# SCH_Arduino-Train-v_2_2026-08-14.net
KiCad netlist of a schematic drawn in EasyEDA
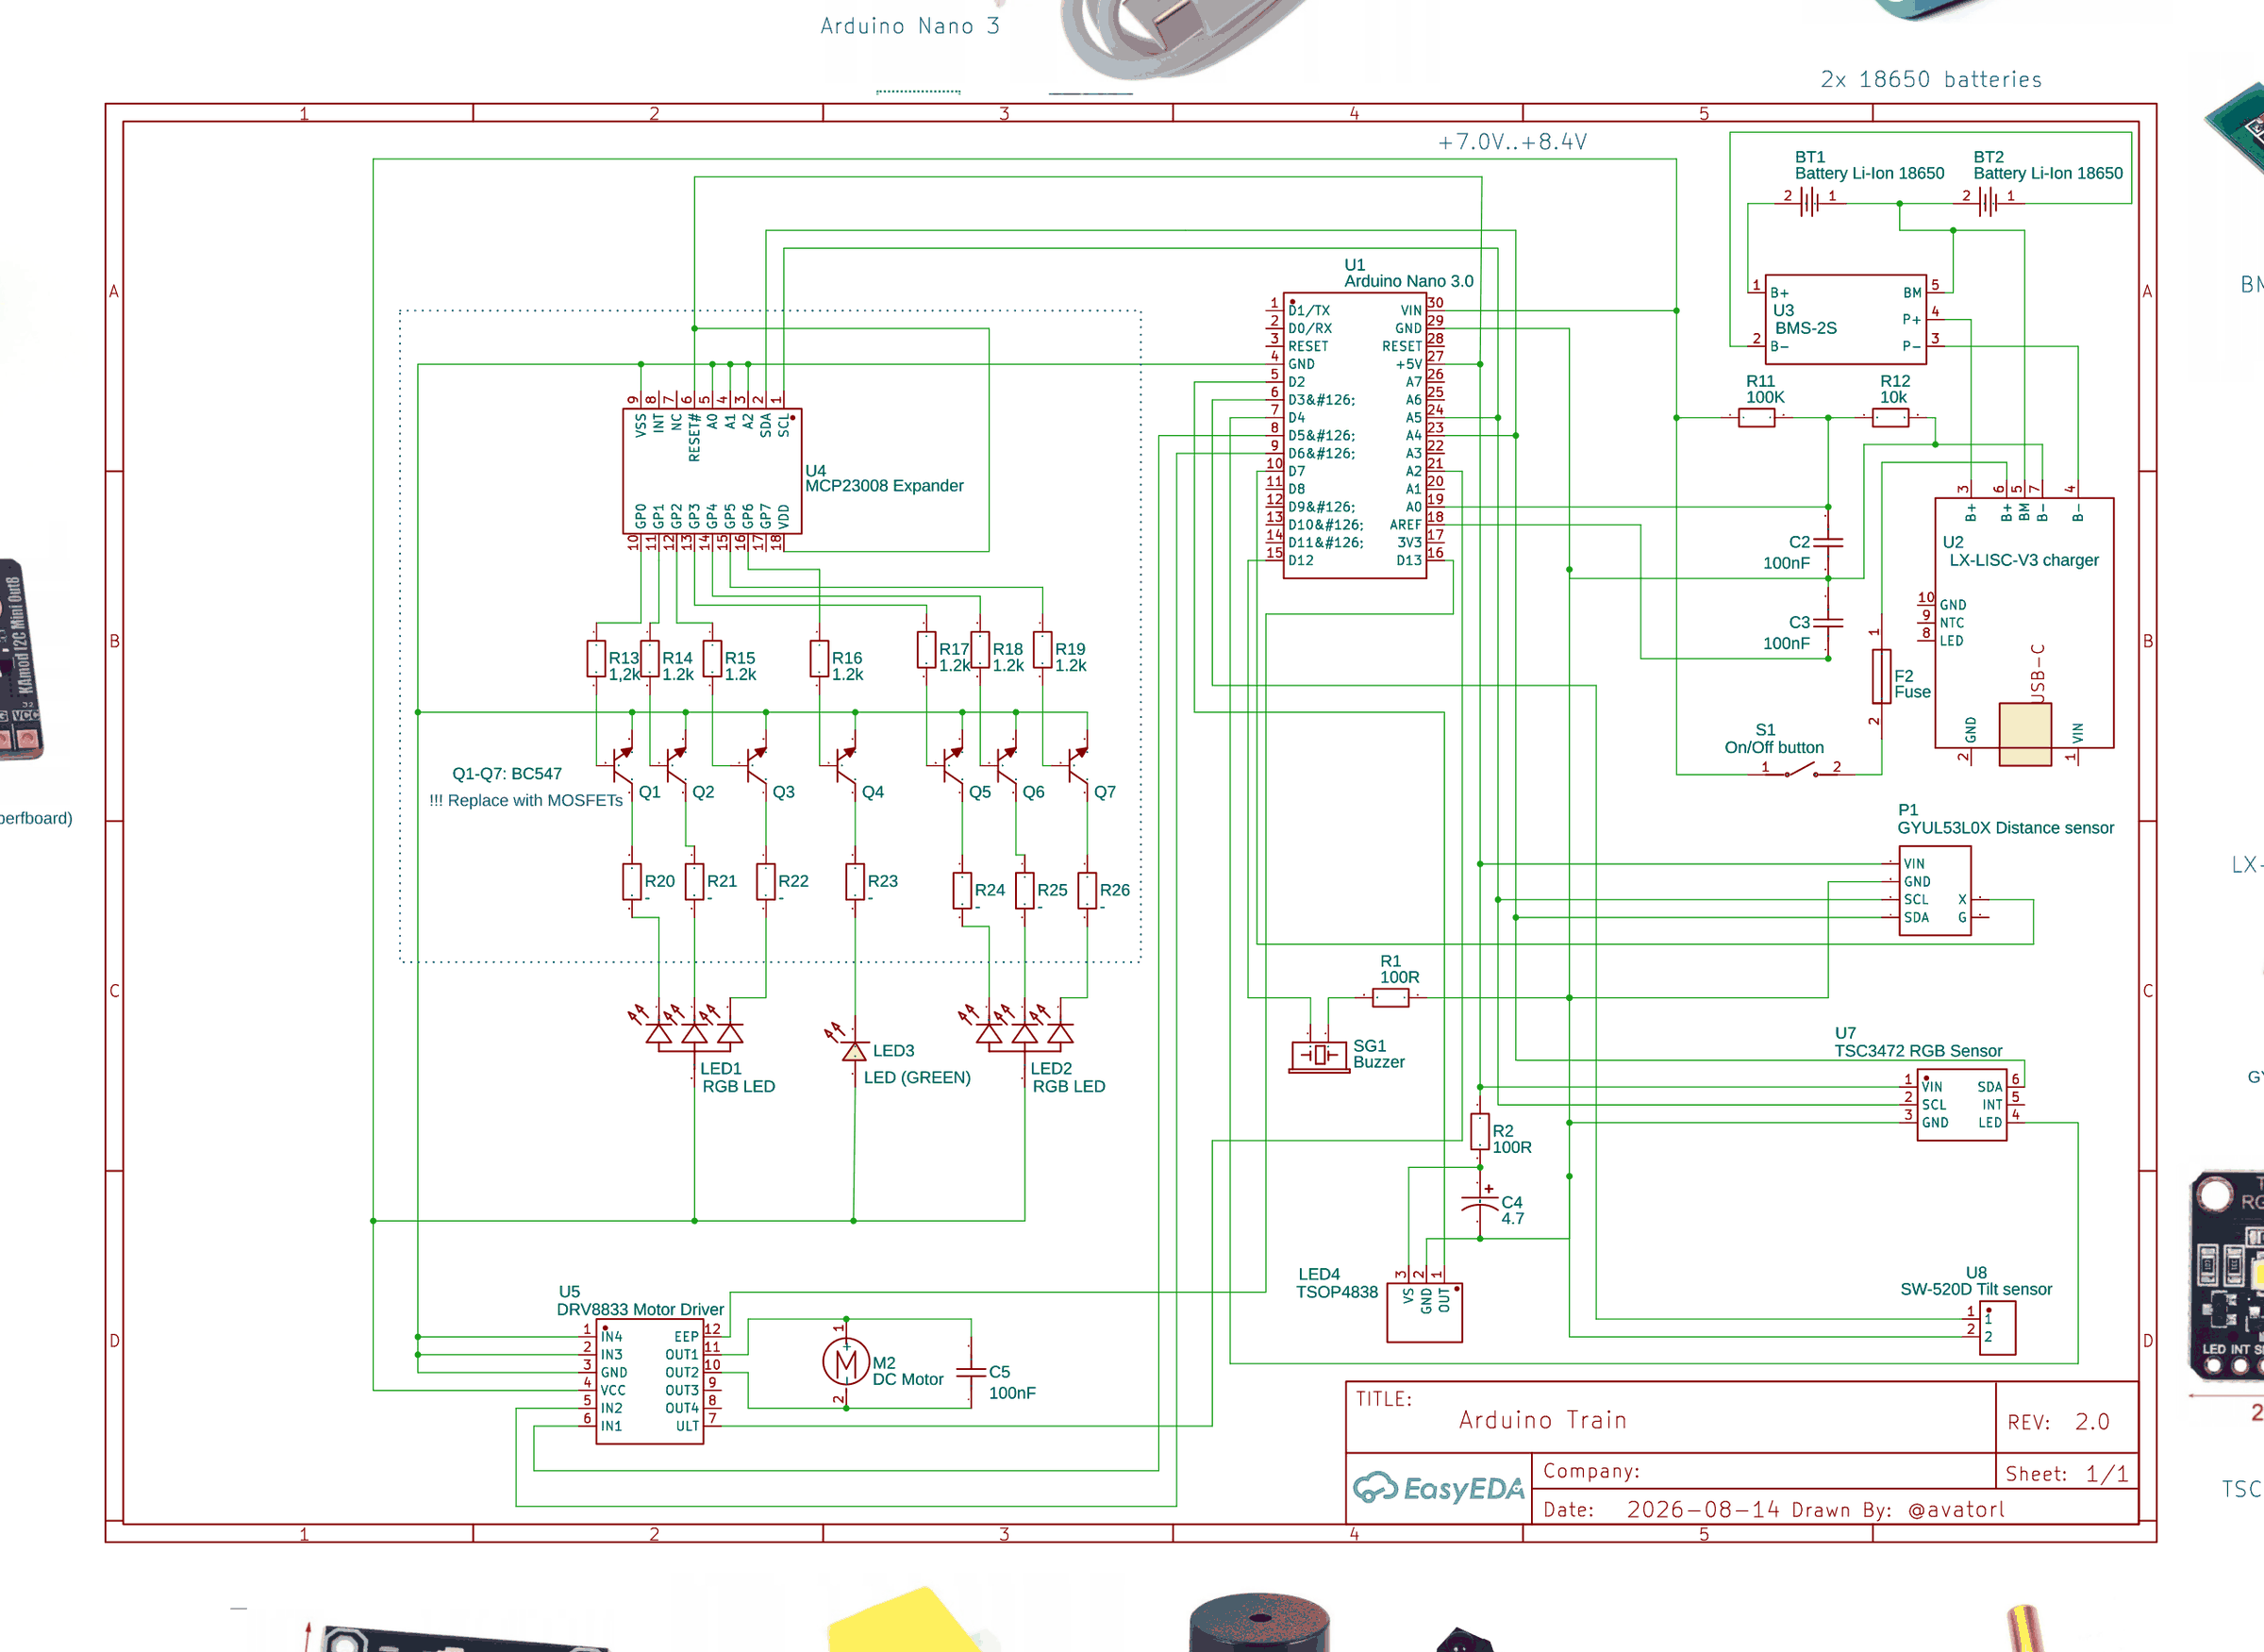
[diagram p0: schematic sheet]

(export (version "E")
  (design (tool "Eeschema 10.0.6"))
  (components
    (comp (ref "BT1")
      (value "Battery Li-Ion 18650")
      (fields
        (field (name "Manufacturer Part") "BH-18650-B1BA002")
        (field (name "Manufacturer") "MYOUNG(美阳)")
      )
      (libsource (lib "") (part "BH-18650-B1BA002"))
    )
    (comp (ref "BT2")
      (value "Battery Li-Ion 18650")
      (fields
        (field (name "Manufacturer Part") "BH-18650-B1BA002")
        (field (name "Manufacturer") "MYOUNG(美阳)")
      )
      (libsource (lib "") (part "BH-18650-B1BA002"))
    )
    (comp (ref "C2") (value "100nF") (libsource (lib "") (part "C_0603_US_1")))
    (comp (ref "C3") (value "100nF") (libsource (lib "") (part "C_0603_US_1")))
    (comp (ref "C4")
      (value "4.7")
      (fields (field (name "Manufacturer Part") "B32672P5105J000") (field (name "Manufacturer") "TDK"))
      (libsource (lib "") (part "C_Tan_SMD_A_US"))
    )
    (comp (ref "C5") (value "100nF") (libsource (lib "") (part "C_0603_US")))
    (comp (ref "F2") (value "Fuse") (libsource (lib "") (part "FUSE BLADE_PCB_MOUNT COPY")))
    (comp (ref "LED1")
      (value "RGB LED")
      (fields (field (name "Manufacturer Part") "3528反贴RGB 6028反贴RGB 缺口蓝色"))
      (libsource (lib "") (part "3528RGB 6028RGB"))
    )
    (comp (ref "LED2")
      (value "RGB LED")
      (fields (field (name "Manufacturer Part") "3528反贴RGB 6028反贴RGB 缺口蓝色"))
      (libsource (lib "") (part "3528RGB 6028RGB"))
    )
    (comp (ref "LED3")
      (value "LED (GREEN)")
      (fields (field (name "Manufacturer Part") "LED三色(Red,Yellow,Green)"))
      (libsource (lib "") (part "LED (GREEN)"))
    )
    (comp (ref "LED4")
      (value "TSOP4838")
      (fields (field (name "Manufacturer") "VISHAY(威世)"))
      (libsource (lib "") (part "TSOP4838"))
    )
    (comp (ref "M2") (value "DC Motor") (libsource (lib "") (part "Motor_DC")))
    (comp (ref "P1")
      (value "GYUL53L0X Distance sensor")
      (fields (field (name "Manufacturer Part") "IDC Box 2X4 2.54MM") (field (name "Manufacturer") "BOOMELE"))
      (libsource (lib "") (part "GYUL53L0X_UPDATED final"))
    )
    (comp (ref "Q1")
      (value "Q1-Q7: BC547")
      (fields
        (field (name "Manufacturer Part") "BC547(RANGE:420-800)")
        (field (name "Manufacturer") "CJ(江苏长电/长晶)")
      )
      (libsource (lib "") (part "BC547"))
    )
    (comp (ref "Q2")
      (value "BC547")
      (fields
        (field (name "Manufacturer Part") "BC547(RANGE:420-800)")
        (field (name "Manufacturer") "CJ(江苏长电/长晶)")
      )
      (libsource (lib "") (part "BC547"))
    )
    (comp (ref "Q3")
      (value "BC547")
      (fields
        (field (name "Manufacturer Part") "BC547(RANGE:420-800)")
        (field (name "Manufacturer") "CJ(江苏长电/长晶)")
      )
      (libsource (lib "") (part "BC547"))
    )
    (comp (ref "Q4")
      (value "BC547")
      (fields
        (field (name "Manufacturer Part") "BC547(RANGE:420-800)")
        (field (name "Manufacturer") "CJ(江苏长电/长晶)")
      )
      (libsource (lib "") (part "BC547"))
    )
    (comp (ref "Q5")
      (value "BC547")
      (fields
        (field (name "Manufacturer Part") "BC547(RANGE:420-800)")
        (field (name "Manufacturer") "CJ(江苏长电/长晶)")
      )
      (libsource (lib "") (part "BC547"))
    )
    (comp (ref "Q6")
      (value "BC547")
      (fields
        (field (name "Manufacturer Part") "BC547(RANGE:420-800)")
        (field (name "Manufacturer") "CJ(江苏长电/长晶)")
      )
      (libsource (lib "") (part "BC547"))
    )
    (comp (ref "Q7")
      (value "BC547")
      (fields
        (field (name "Manufacturer Part") "BC547(RANGE:420-800)")
        (field (name "Manufacturer") "CJ(江苏长电/长晶)")
      )
      (libsource (lib "") (part "BC547"))
    )
    (comp (ref "R1") (value "100R") (libsource (lib "") (part "R_0603_EU_2")))
    (comp (ref "R2") (value "100R") (libsource (lib "") (part "R_0603_EU")))
    (comp (ref "R11") (value "100K") (libsource (lib "") (part "R_0603_EU_1")))
    (comp (ref "R12") (value "10k") (libsource (lib "") (part "R_0603_EU_1")))
    (comp (ref "R13") (value "1,2k") (libsource (lib "") (part "R_0603_EU")))
    (comp (ref "R14") (value "1.2k") (libsource (lib "") (part "R_0603_EU")))
    (comp (ref "R15") (value "1.2k") (libsource (lib "") (part "R_0603_EU")))
    (comp (ref "R16") (value "1.2k") (libsource (lib "") (part "R_0603_EU")))
    (comp (ref "R17") (value "1.2k") (libsource (lib "") (part "R_0603_EU")))
    (comp (ref "R18") (value "1.2k") (libsource (lib "") (part "R_0603_EU")))
    (comp (ref "R19") (value "1.2k") (libsource (lib "") (part "R_0603_EU")))
    (comp (ref "R20") (value "-") (libsource (lib "") (part "R_0603_EU")))
    (comp (ref "R21") (value "-") (libsource (lib "") (part "R_0603_EU")))
    (comp (ref "R22") (value "-") (libsource (lib "") (part "R_0603_EU")))
    (comp (ref "R23") (value "-") (libsource (lib "") (part "R_0603_EU")))
    (comp (ref "R24") (value "-") (libsource (lib "") (part "R_0603_EU")))
    (comp (ref "R25") (value "-") (libsource (lib "") (part "R_0603_EU")))
    (comp (ref "R26") (value "-") (libsource (lib "") (part "R_0603_EU")))
    (comp (ref "S1")
      (value "On/Off button")
      (fields (field (name "Manufacturer Part") "BUTTON"))
      (libsource (lib "") (part "BUTTON"))
    )
    (comp (ref "SG1") (value "Buzzer") (libsource (lib "") (part "BUZZER")))
    (comp (ref "U1")
      (value "Arduino Nano 3.0")
      (fields (field (name "Manufacturer Part") "ARDUINO_NANO"))
      (libsource (lib "") (part "ARDUINO_NANO"))
    )
    (comp (ref "U2") (value "LX-LISC-V3 charger") (libsource (lib "") (part "LX-LISC-V1")))
    (comp (ref "U3")
      (value "BMS-2S")
      (fields (field (name "Manufacturer Part") "HX-2S-D01"))
      (libsource (lib "") (part "2S 3A-10A Lithium Li-ion 18650 Battery BMS Protection PCB Board 7.4v/8.4V"))
    )
    (comp (ref "U4")
      (value "MCP23008 Expander")
      (fields
        (field (name "Manufacturer Part") "MCP23008-E/P")
        (field (name "Manufacturer") "MICROCHIP(美国微芯)")
      )
      (libsource (lib "") (part "MCP23008-E/P"))
    )
    (comp (ref "U5")
      (value "DRV8833 Motor Driver")
      (fields (field (name "Manufacturer Part") "DRV8833"))
      (libsource (lib "") (part "DRV8833 - Motor Driver"))
    )
    (comp (ref "U7")
      (value "TSC3472 RGB Sensor")
      (fields (field (name "Manufacturer Part") "TCS34725FN") (field (name "Manufacturer") "ams(艾迈斯半导体)"))
      (libsource (lib "") (part "TCS34725FN"))
    )
    (comp (ref "U8")
      (value "SW-520D Tilt sensor")
      (fields (field (name "Manufacturer Part") "SW-520D") (field (name "Manufacturer") "SHOU HAN(首韩)"))
      (libsource (lib "") (part "SW-520D"))
    )
  )
  (nets
    (net (code "1") (name "Net-(F2-Pad1)") (class "Default")
      (node (ref "F2") (pin "1") (pinfunction "1_1") (pintype "unspecified"))
      (node (ref "U2") (pin "6") (pinfunction "B+_6") (pintype "unspecified"))
    )
    (net (code "2") (name "Net-(F2-Pad2)") (class "Default")
      (node (ref "F2") (pin "2") (pinfunction "2_2") (pintype "unspecified"))
      (node (ref "S1") (pin "2") (pinfunction "2_2") (pintype "unspecified"))
    )
    (net (code "3") (name "Net-(LED1-A)") (class "Default")
      (node (ref "LED1") (pin "3") (pinfunction "A_3") (pintype "unspecified"))
      (node (ref "LED2") (pin "3") (pinfunction "A_3") (pintype "unspecified"))
      (node (ref "LED3") (pin "2") (pinfunction "2_2") (pintype "unspecified"))
      (node (ref "R11") (pin "1") (pinfunction "1_1") (pintype "unspecified"))
      (node (ref "S1") (pin "1") (pinfunction "1_1") (pintype "unspecified"))
      (node (ref "U1") (pin "30") (pinfunction "VIN_30") (pintype "unspecified"))
      (node (ref "U5") (pin "4") (pinfunction "VCC_4") (pintype "unspecified"))
    )
    (net (code "4") (name "Net-(LED1-B)") (class "Default")
      (node (ref "LED1") (pin "1") (pinfunction "B_1") (pintype "unspecified"))
      (node (ref "R21") (pin "2") (pinfunction "2_2") (pintype "unspecified"))
    )
    (net (code "5") (name "Net-(LED1-G)") (class "Default")
      (node (ref "LED1") (pin "4") (pinfunction "G_4") (pintype "unspecified"))
      (node (ref "R20") (pin "2") (pinfunction "2_2") (pintype "unspecified"))
    )
    (net (code "6") (name "Net-(LED1-R)") (class "Default")
      (node (ref "LED1") (pin "2") (pinfunction "R_2") (pintype "unspecified"))
      (node (ref "R22") (pin "2") (pinfunction "2_2") (pintype "unspecified"))
    )
    (net (code "7") (name "Net-(LED2-B)") (class "Default")
      (node (ref "LED2") (pin "1") (pinfunction "B_1") (pintype "unspecified"))
      (node (ref "R25") (pin "2") (pinfunction "2_2") (pintype "unspecified"))
    )
    (net (code "8") (name "Net-(LED2-G)") (class "Default")
      (node (ref "LED2") (pin "4") (pinfunction "G_4") (pintype "unspecified"))
      (node (ref "R24") (pin "2") (pinfunction "2_2") (pintype "unspecified"))
    )
    (net (code "9") (name "Net-(LED2-R)") (class "Default")
      (node (ref "LED2") (pin "2") (pinfunction "R_2") (pintype "unspecified"))
      (node (ref "R26") (pin "2") (pinfunction "2_2") (pintype "unspecified"))
    )
    (net (code "10") (name "Net-(LED3-Pad1)") (class "Default")
      (node (ref "LED3") (pin "1") (pinfunction "1_1") (pintype "unspecified"))
      (node (ref "R23") (pin "2") (pinfunction "2_2") (pintype "unspecified"))
    )
    (net (code "11") (name "Net-(LED4-GND)") (class "Default")
      (node (ref "C2") (pin "1") (pinfunction "1_1") (pintype "unspecified"))
      (node (ref "C3") (pin "2") (pinfunction "2_2") (pintype "unspecified"))
      (node (ref "C4") (pin "2") (pinfunction "2_2") (pintype "unspecified"))
      (node (ref "LED4") (pin "2") (pinfunction "GND_2") (pintype "unspecified"))
      (node (ref "P1") (pin "3") (pinfunction "GND_3") (pintype "unspecified"))
      (node (ref "R1") (pin "1") (pinfunction "1_1") (pintype "unspecified"))
      (node (ref "R12") (pin "2") (pinfunction "2_2") (pintype "unspecified"))
      (node (ref "U1") (pin "29") (pinfunction "GND_29") (pintype "unspecified"))
      (node (ref "U2") (pin "7") (pinfunction "B-_7") (pintype "unspecified"))
      (node (ref "U7") (pin "3") (pinfunction "GND_3") (pintype "unspecified"))
      (node (ref "U8") (pin "2") (pinfunction "2_2") (pintype "unspecified"))
    )
    (net (code "12") (name "Net-(LED4-OUT)") (class "Default")
      (node (ref "LED4") (pin "1") (pinfunction "OUT_1") (pintype "unspecified"))
      (node (ref "U1") (pin "5") (pinfunction "D2_5") (pintype "unspecified"))
    )
    (net (code "13") (name "Net-(LED4-VS)") (class "Default")
      (node (ref "C4") (pin "1") (pinfunction "1_1") (pintype "unspecified"))
      (node (ref "LED4") (pin "3") (pinfunction "VS_3") (pintype "unspecified"))
      (node (ref "R2") (pin "2") (pinfunction "2_2") (pintype "unspecified"))
    )
    (net (code "14") (name "Net-(M2-+)") (class "Default")
      (node (ref "C5") (pin "2") (pinfunction "2_2") (pintype "unspecified"))
      (node (ref "M2") (pin "1") (pinfunction "+_1") (pintype "unspecified"))
      (node (ref "U5") (pin "11") (pinfunction "OUT1_11") (pintype "unspecified"))
    )
    (net (code "15") (name "Net-(M2--)") (class "Default")
      (node (ref "C5") (pin "1") (pinfunction "1_1") (pintype "unspecified"))
      (node (ref "M2") (pin "2") (pinfunction "-_2") (pintype "unspecified"))
      (node (ref "U5") (pin "10") (pinfunction "OUT2_10") (pintype "unspecified"))
    )
    (net (code "16") (name "Net-(P1-SCL)") (class "Default")
      (node (ref "P1") (pin "5") (pinfunction "SCL_5") (pintype "unspecified"))
      (node (ref "U1") (pin "24") (pinfunction "A5_24") (pintype "unspecified"))
      (node (ref "U4") (pin "1") (pinfunction "SCL_1") (pintype "unspecified"))
      (node (ref "U7") (pin "2") (pinfunction "SCL_2") (pintype "unspecified"))
    )
    (net (code "17") (name "Net-(P1-SDA)") (class "Default")
      (node (ref "P1") (pin "7") (pinfunction "SDA_7") (pintype "unspecified"))
      (node (ref "U1") (pin "23") (pinfunction "A4_23") (pintype "unspecified"))
      (node (ref "U4") (pin "2") (pinfunction "SDA_2") (pintype "unspecified"))
      (node (ref "U7") (pin "6") (pinfunction "SDA_6") (pintype "unspecified"))
    )
    (net (code "18") (name "Net-(P1-VIN)") (class "Default")
      (node (ref "P1") (pin "1") (pinfunction "VIN_1") (pintype "unspecified"))
      (node (ref "R2") (pin "1") (pinfunction "1_1") (pintype "unspecified"))
      (node (ref "U1") (pin "27") (pinfunction "+5V_27") (pintype "unspecified"))
      (node (ref "U4") (pin "18") (pinfunction "VDD_18") (pintype "unspecified"))
      (node (ref "U4") (pin "6") (pinfunction "RESET#_6") (pintype "unspecified"))
      (node (ref "U7") (pin "1") (pinfunction "VIN_1") (pintype "unspecified"))
    )
    (net (code "19") (name "Net-(P1-X)") (class "Default")
      (node (ref "P1") (pin "6") (pinfunction "X_6") (pintype "unspecified"))
      (node (ref "U1") (pin "10") (pinfunction "D7_10") (pintype "unspecified"))
    )
    (net (code "20") (name "Net-(Q1-B)") (class "Default")
      (node (ref "Q1") (pin "2") (pinfunction "B_2") (pintype "unspecified"))
      (node (ref "R13") (pin "2") (pinfunction "2_2") (pintype "unspecified"))
    )
    (net (code "21") (name "Net-(Q1-C)") (class "Default")
      (node (ref "Q1") (pin "1") (pinfunction "C_1") (pintype "unspecified"))
      (node (ref "R20") (pin "1") (pinfunction "1_1") (pintype "unspecified"))
    )
    (net (code "22") (name "Net-(Q1-E)") (class "Default")
      (node (ref "Q1") (pin "3") (pinfunction "E_3") (pintype "unspecified"))
      (node (ref "Q2") (pin "3") (pinfunction "E_3") (pintype "unspecified"))
      (node (ref "Q3") (pin "3") (pinfunction "E_3") (pintype "unspecified"))
      (node (ref "Q4") (pin "3") (pinfunction "E_3") (pintype "unspecified"))
      (node (ref "Q5") (pin "3") (pinfunction "E_3") (pintype "unspecified"))
      (node (ref "Q6") (pin "3") (pinfunction "E_3") (pintype "unspecified"))
      (node (ref "Q7") (pin "3") (pinfunction "E_3") (pintype "unspecified"))
      (node (ref "U1") (pin "4") (pinfunction "GND_4") (pintype "unspecified"))
      (node (ref "U4") (pin "3") (pinfunction "A2_3") (pintype "unspecified"))
      (node (ref "U4") (pin "4") (pinfunction "A1_4") (pintype "unspecified"))
      (node (ref "U4") (pin "5") (pinfunction "A0_5") (pintype "unspecified"))
      (node (ref "U4") (pin "9") (pinfunction "VSS_9") (pintype "unspecified"))
      (node (ref "U5") (pin "1") (pinfunction "IN4_1") (pintype "unspecified"))
      (node (ref "U5") (pin "2") (pinfunction "IN3_2") (pintype "unspecified"))
      (node (ref "U5") (pin "3") (pinfunction "GND_3") (pintype "unspecified"))
    )
    (net (code "23") (name "Net-(Q2-B)") (class "Default")
      (node (ref "Q2") (pin "2") (pinfunction "B_2") (pintype "unspecified"))
      (node (ref "R14") (pin "2") (pinfunction "2_2") (pintype "unspecified"))
    )
    (net (code "24") (name "Net-(Q2-C)") (class "Default")
      (node (ref "Q2") (pin "1") (pinfunction "C_1") (pintype "unspecified"))
      (node (ref "R21") (pin "1") (pinfunction "1_1") (pintype "unspecified"))
    )
    (net (code "25") (name "Net-(Q3-B)") (class "Default")
      (node (ref "Q3") (pin "2") (pinfunction "B_2") (pintype "unspecified"))
      (node (ref "R15") (pin "2") (pinfunction "2_2") (pintype "unspecified"))
    )
    (net (code "26") (name "Net-(Q3-C)") (class "Default")
      (node (ref "Q3") (pin "1") (pinfunction "C_1") (pintype "unspecified"))
      (node (ref "R22") (pin "1") (pinfunction "1_1") (pintype "unspecified"))
    )
    (net (code "27") (name "Net-(Q4-B)") (class "Default")
      (node (ref "Q4") (pin "2") (pinfunction "B_2") (pintype "unspecified"))
      (node (ref "R16") (pin "2") (pinfunction "2_2") (pintype "unspecified"))
    )
    (net (code "28") (name "Net-(Q4-C)") (class "Default")
      (node (ref "Q4") (pin "1") (pinfunction "C_1") (pintype "unspecified"))
      (node (ref "R23") (pin "1") (pinfunction "1_1") (pintype "unspecified"))
    )
    (net (code "29") (name "Net-(Q5-B)") (class "Default")
      (node (ref "Q5") (pin "2") (pinfunction "B_2") (pintype "unspecified"))
      (node (ref "R17") (pin "2") (pinfunction "2_2") (pintype "unspecified"))
    )
    (net (code "30") (name "Net-(Q5-C)") (class "Default")
      (node (ref "Q5") (pin "1") (pinfunction "C_1") (pintype "unspecified"))
      (node (ref "R24") (pin "1") (pinfunction "1_1") (pintype "unspecified"))
    )
    (net (code "31") (name "Net-(Q6-B)") (class "Default")
      (node (ref "Q6") (pin "2") (pinfunction "B_2") (pintype "unspecified"))
      (node (ref "R18") (pin "2") (pinfunction "2_2") (pintype "unspecified"))
    )
    (net (code "32") (name "Net-(Q6-C)") (class "Default")
      (node (ref "Q6") (pin "1") (pinfunction "C_1") (pintype "unspecified"))
      (node (ref "R25") (pin "1") (pinfunction "1_1") (pintype "unspecified"))
    )
    (net (code "33") (name "Net-(Q7-B)") (class "Default")
      (node (ref "Q7") (pin "2") (pinfunction "B_2") (pintype "unspecified"))
      (node (ref "R19") (pin "2") (pinfunction "2_2") (pintype "unspecified"))
    )
    (net (code "34") (name "Net-(Q7-C)") (class "Default")
      (node (ref "Q7") (pin "1") (pinfunction "C_1") (pintype "unspecified"))
      (node (ref "R26") (pin "1") (pinfunction "1_1") (pintype "unspecified"))
    )
    (net (code "35") (name "Net-(R1-Pad2)") (class "Default")
      (node (ref "R1") (pin "2") (pinfunction "2_2") (pintype "unspecified"))
      (node (ref "SG1") (pin "1") (pinfunction "1_1") (pintype "unspecified"))
    )
    (net (code "36") (name "Net-(U1-A0)") (class "Default")
      (node (ref "C2") (pin "2") (pinfunction "2_2") (pintype "unspecified"))
      (node (ref "R11") (pin "2") (pinfunction "2_2") (pintype "unspecified"))
      (node (ref "R12") (pin "1") (pinfunction "1_1") (pintype "unspecified"))
      (node (ref "U1") (pin "19") (pinfunction "A0_19") (pintype "unspecified"))
    )
    (net (code "37") (name "Net-(U1-A2)") (class "Default")
      (node (ref "U1") (pin "21") (pinfunction "A2_21") (pintype "unspecified"))
      (node (ref "U5") (pin "7") (pinfunction "ULT_7") (pintype "unspecified"))
    )
    (net (code "38") (name "Net-(U1-AREF)") (class "Default")
      (node (ref "C3") (pin "1") (pinfunction "1_1") (pintype "unspecified"))
      (node (ref "U1") (pin "18") (pinfunction "AREF_18") (pintype "unspecified"))
    )
    (net (code "39") (name "Net-(U1-D3&#126;)") (class "Default")
      (node (ref "U1") (pin "6") (pinfunction "D3&#126;_6") (pintype "unspecified"))
      (node (ref "U8") (pin "1") (pinfunction "1_1") (pintype "unspecified"))
    )
    (net (code "40") (name "Net-(U1-D4)") (class "Default")
      (node (ref "U1") (pin "7") (pinfunction "D4_7") (pintype "unspecified"))
      (node (ref "U7") (pin "4") (pinfunction "LED_4") (pintype "unspecified"))
    )
    (net (code "41") (name "Net-(U1-D5&#126;)") (class "Default")
      (node (ref "U1") (pin "8") (pinfunction "D5&#126;_8") (pintype "unspecified"))
      (node (ref "U5") (pin "6") (pinfunction "IN1_6") (pintype "unspecified"))
    )
    (net (code "42") (name "Net-(U1-D6&#126;)") (class "Default")
      (node (ref "U1") (pin "9") (pinfunction "D6&#126;_9") (pintype "unspecified"))
      (node (ref "U5") (pin "5") (pinfunction "IN2_5") (pintype "unspecified"))
    )
    (net (code "43") (name "Net-(U1-D12)") (class "Default")
      (node (ref "SG1") (pin "2") (pinfunction "2_2") (pintype "unspecified"))
      (node (ref "U1") (pin "15") (pinfunction "D12_15") (pintype "unspecified"))
    )
    (net (code "44") (name "Net-(U1-D13)") (class "Default")
      (node (ref "U1") (pin "16") (pinfunction "D13_16") (pintype "unspecified"))
      (node (ref "U5") (pin "12") (pinfunction "EEP_12") (pintype "unspecified"))
    )
    (net (code "45") (name "Net-(U2-BM)") (class "Default")
      (node (ref "BT1") (pin "1") (pinfunction "1_1") (pintype "input"))
      (node (ref "BT2") (pin "2") (pinfunction "2_2") (pintype "input"))
      (node (ref "U2") (pin "5") (pinfunction "BM_5") (pintype "unspecified"))
      (node (ref "U3") (pin "5") (pinfunction "BM_5") (pintype "unspecified"))
    )
    (net (code "46") (name "Net-(U3-B+)") (class "Default")
      (node (ref "BT1") (pin "2") (pinfunction "2_2") (pintype "input"))
      (node (ref "U3") (pin "1") (pinfunction "B+_1") (pintype "unspecified"))
    )
    (net (code "47") (name "Net-(U3-B-)") (class "Default")
      (node (ref "BT2") (pin "1") (pinfunction "1_1") (pintype "input"))
      (node (ref "U3") (pin "2") (pinfunction "B-_2") (pintype "unspecified"))
    )
    (net (code "48") (name "Net-(U3-P+)") (class "Default")
      (node (ref "U2") (pin "3") (pinfunction "B+_3") (pintype "unspecified"))
      (node (ref "U3") (pin "4") (pinfunction "P+_4") (pintype "unspecified"))
    )
    (net (code "49") (name "Net-(U3-P-)") (class "Default")
      (node (ref "U2") (pin "4") (pinfunction "B-_4") (pintype "unspecified"))
      (node (ref "U3") (pin "3") (pinfunction "P-_3") (pintype "unspecified"))
    )
    (net (code "50") (name "Net-(U4-GP0)") (class "Default")
      (node (ref "R13") (pin "1") (pinfunction "1_1") (pintype "unspecified"))
      (node (ref "U4") (pin "10") (pinfunction "GP0_10") (pintype "unspecified"))
    )
    (net (code "51") (name "Net-(U4-GP1)") (class "Default")
      (node (ref "R14") (pin "1") (pinfunction "1_1") (pintype "unspecified"))
      (node (ref "U4") (pin "11") (pinfunction "GP1_11") (pintype "unspecified"))
    )
    (net (code "52") (name "Net-(U4-GP2)") (class "Default")
      (node (ref "R15") (pin "1") (pinfunction "1_1") (pintype "unspecified"))
      (node (ref "U4") (pin "12") (pinfunction "GP2_12") (pintype "unspecified"))
    )
    (net (code "53") (name "Net-(U4-GP3)") (class "Default")
      (node (ref "R17") (pin "1") (pinfunction "1_1") (pintype "unspecified"))
      (node (ref "U4") (pin "13") (pinfunction "GP3_13") (pintype "unspecified"))
    )
    (net (code "54") (name "Net-(U4-GP4)") (class "Default")
      (node (ref "R18") (pin "1") (pinfunction "1_1") (pintype "unspecified"))
      (node (ref "U4") (pin "14") (pinfunction "GP4_14") (pintype "unspecified"))
    )
    (net (code "55") (name "Net-(U4-GP5)") (class "Default")
      (node (ref "R19") (pin "1") (pinfunction "1_1") (pintype "unspecified"))
      (node (ref "U4") (pin "15") (pinfunction "GP5_15") (pintype "unspecified"))
    )
    (net (code "56") (name "Net-(U4-GP6)") (class "Default")
      (node (ref "R16") (pin "1") (pinfunction "1_1") (pintype "unspecified"))
      (node (ref "U4") (pin "16") (pinfunction "GP6_16") (pintype "unspecified"))
    )
    (net (code "57") (name "unconnected-(P1-G-Pad8)") (class "Default")
      (node (ref "P1") (pin "8") (pinfunction "G_8") (pintype "unspecified"))
    )
    (net (code "58") (name "unconnected-(U1-3V3-Pad17)") (class "Default")
      (node (ref "U1") (pin "17") (pinfunction "3V3_17") (pintype "unspecified"))
    )
    (net (code "59") (name "unconnected-(U1-A1-Pad20)") (class "Default")
      (node (ref "U1") (pin "20") (pinfunction "A1_20") (pintype "unspecified"))
    )
    (net (code "60") (name "unconnected-(U1-A3-Pad22)") (class "Default")
      (node (ref "U1") (pin "22") (pinfunction "A3_22") (pintype "unspecified"))
    )
    (net (code "61") (name "unconnected-(U1-A6-Pad25)") (class "Default")
      (node (ref "U1") (pin "25") (pinfunction "A6_25") (pintype "unspecified"))
    )
    (net (code "62") (name "unconnected-(U1-A7-Pad26)") (class "Default")
      (node (ref "U1") (pin "26") (pinfunction "A7_26") (pintype "unspecified"))
    )
    (net (code "63") (name "unconnected-(U1-D0{slash}RX-Pad2)") (class "Default")
      (node (ref "U1") (pin "2") (pinfunction "D0/RX_2") (pintype "unspecified"))
    )
    (net (code "64") (name "unconnected-(U1-D1{slash}TX-Pad1)") (class "Default")
      (node (ref "U1") (pin "1") (pinfunction "D1/TX_1") (pintype "unspecified"))
    )
    (net (code "65") (name "unconnected-(U1-D8-Pad11)") (class "Default")
      (node (ref "U1") (pin "11") (pinfunction "D8_11") (pintype "unspecified"))
    )
    (net (code "66") (name "unconnected-(U1-D9&#126;-Pad12)") (class "Default")
      (node (ref "U1") (pin "12") (pinfunction "D9&#126;_12") (pintype "unspecified"))
    )
    (net (code "67") (name "unconnected-(U1-D10&#126;-Pad13)") (class "Default")
      (node (ref "U1") (pin "13") (pinfunction "D10&#126;_13") (pintype "unspecified"))
    )
    (net (code "68") (name "unconnected-(U1-D11&#126;-Pad14)") (class "Default")
      (node (ref "U1") (pin "14") (pinfunction "D11&#126;_14") (pintype "unspecified"))
    )
    (net (code "69") (name "unconnected-(U1-RESET-Pad3)") (class "Default")
      (node (ref "U1") (pin "3") (pinfunction "RESET_3") (pintype "unspecified"))
    )
    (net (code "70") (name "unconnected-(U1-RESET-Pad28)") (class "Default")
      (node (ref "U1") (pin "28") (pinfunction "RESET_28") (pintype "unspecified"))
    )
    (net (code "71") (name "unconnected-(U2-GND-Pad2)") (class "Default")
      (node (ref "U2") (pin "2") (pinfunction "GND_2") (pintype "unspecified"))
    )
    (net (code "72") (name "unconnected-(U2-GND-Pad10)") (class "Default")
      (node (ref "U2") (pin "10") (pinfunction "GND_10") (pintype "unspecified"))
    )
    (net (code "73") (name "unconnected-(U2-LED-Pad8)") (class "Default")
      (node (ref "U2") (pin "8") (pinfunction "LED_8") (pintype "unspecified"))
    )
    (net (code "74") (name "unconnected-(U2-NTC-Pad9)") (class "Default")
      (node (ref "U2") (pin "9") (pinfunction "NTC_9") (pintype "unspecified"))
    )
    (net (code "75") (name "unconnected-(U2-VIN-Pad1)") (class "Default")
      (node (ref "U2") (pin "1") (pinfunction "VIN_1") (pintype "unspecified"))
    )
    (net (code "76") (name "unconnected-(U4-GP7-Pad17)") (class "Default")
      (node (ref "U4") (pin "17") (pinfunction "GP7_17") (pintype "unspecified"))
    )
    (net (code "77") (name "unconnected-(U4-INT-Pad8)") (class "Default")
      (node (ref "U4") (pin "8") (pinfunction "INT_8") (pintype "unspecified"))
    )
    (net (code "78") (name "unconnected-(U4-NC-Pad7)") (class "Default")
      (node (ref "U4") (pin "7") (pinfunction "NC_7") (pintype "unspecified"))
    )
    (net (code "79") (name "unconnected-(U5-OUT3-Pad9)") (class "Default")
      (node (ref "U5") (pin "9") (pinfunction "OUT3_9") (pintype "unspecified"))
    )
    (net (code "80") (name "unconnected-(U5-OUT4-Pad8)") (class "Default")
      (node (ref "U5") (pin "8") (pinfunction "OUT4_8") (pintype "unspecified"))
    )
    (net (code "81") (name "unconnected-(U7-INT-Pad5)") (class "Default")
      (node (ref "U7") (pin "5") (pinfunction "INT_5") (pintype "unspecified"))
    )
  )
)
